# tachometer.net
KiCad netlist of a schematic drawn in Altium Designer
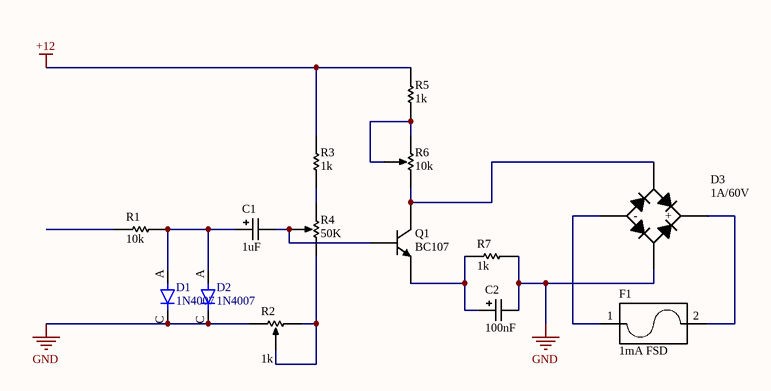
[diagram p0: tachometer.SchDoc]

(export (version "E")
  (design (tool "Eeschema 10.0.6"))
  (components
    (comp (ref "C1")
      (value "1uF")
      (footprint "CAPAE660X660R_PAN")
      (description "CAP ALUM 100UF 35V 20% SMD")
      (libsource (lib "CAP_ELE_AU_TQ_6.6X6.6_35V_PAN") (part "100uF_EEE-TQV101XAP_PAN"))
    )
    (comp (ref "C2")
      (value "100nF")
      (footprint "CAPAE660X660R_PAN")
      (description "CAP ALUM 100UF 35V 20% SMD")
      (libsource (lib "CAP_ELE_AU_TQ_6.6X6.6_35V_PAN") (part "100uF_EEE-TQV101XAP_PAN"))
    )
    (comp (ref "D1")
      (value "1N4007")
      (footprint "DIOAD1060W80L520D270")
      (description "Diode Standard 1000V 1A Through Hole DO-204AL _DO-41_")
      (fields (field (name "MF") "ON Semiconductor"))
      (libsource (lib "1N4007") (part "1N4007"))
    )
    (comp (ref "D2")
      (value "1N4007")
      (footprint "DIOAD1060W80L520D270")
      (description "Diode Standard 1000V 1A Through Hole DO-204AL _DO-41_")
      (fields (field (name "MF") "ON Semiconductor"))
      (libsource (lib "1N4007") (part "1N4007"))
    )
    (comp (ref "D3")
      (value "1A/60V")
      (footprint "SOIC127P670X270-8N_MCC")
      (description "DIODE SCHOTTKY 1A 60V MBS-1")
      (libsource (lib "DIO_BRIDGE_RECTIFIER_MB_SMD_MCC") (part "MB16S-TP_MCC"))
    )
    (comp (ref "F1")
      (value "1mA FSD")
      (footprint "NANO-452_LIT")
      (description "FUSE BOARD MNT 2A 125VAC/VDC SMD")
      (libsource (lib "FUSE_SLOW_NANO-452_LIT") (part "2A_0452002.MRL_LIT"))
    )
    (comp (ref "Q1")
      (value "BC107")
      (footprint "SOT95P230X110-3N_PHY")
      (libsource (lib "TRA_GP_NPN_SOT23_PHY") (part "BC817_SOT23"))
    )
    (comp (ref "R1")
      (value "10k")
      (footprint "RESC1508X05R_VIS")
      (description "POWER METAL STRIP RESISTOR 0.1W 1%")
      (libsource (lib "RES_MTF_AU_WSL_0603_1%_0.1W_VIS") (part "WSL0603R0150FEA_VIS"))
    )
    (comp (ref "R2")
      (value "1k")
      (footprint "TRIM_ST4ETB503_COP")
      (description "TRIMMER 5K OHM 0.25W SMD")
      (libsource (lib "POT_ST4_5mm_20%_0.25W_COP") (part "5K_ST4ETB502_COP"))
    )
    (comp (ref "R3")
      (value "1k")
      (footprint "RESC1508X05R_VIS")
      (description "POWER METAL STRIP RESISTOR 0.1W 1%")
      (libsource (lib "RES_MTF_AU_WSL_0603_1%_0.1W_VIS") (part "WSL0603R0150FEA_VIS"))
    )
    (comp (ref "R4")
      (value "50K")
      (footprint "TRIM_ST4ETB503_COP")
      (description "TRIMMER 5K OHM 0.25W SMD")
      (libsource (lib "POT_ST4_5mm_20%_0.25W_COP") (part "5K_ST4ETB502_COP"))
    )
    (comp (ref "R5")
      (value "1k")
      (footprint "RESC1508X05R_VIS")
      (description "POWER METAL STRIP RESISTOR 0.1W 1%")
      (libsource (lib "RES_MTF_AU_WSL_0603_1%_0.1W_VIS") (part "WSL0603R0150FEA_VIS"))
    )
    (comp (ref "R6")
      (value "10k")
      (footprint "TRIM_ST4ETB503_COP")
      (description "TRIMMER 5K OHM 0.25W SMD")
      (libsource (lib "POT_ST4_5mm_20%_0.25W_COP") (part "5K_ST4ETB502_COP"))
    )
    (comp (ref "R7")
      (value "1k")
      (footprint "RESC1508X05R_VIS")
      (description "POWER METAL STRIP RESISTOR 0.1W 1%")
      (libsource (lib "RES_MTF_AU_WSL_0603_1%_0.1W_VIS") (part "WSL0603R0150FEA_VIS"))
    )
  )
  (nets
    (net (code "1") (name "+12") (class "Default")
      (node (ref "R3") (pin "2") (pinfunction "2_2") (pintype "passive"))
      (node (ref "R5") (pin "2") (pinfunction "2_2") (pintype "passive"))
    )
    (net (code "2") (name "GND") (class "Default")
      (node (ref "C2") (pin "2") (pinfunction "2_2") (pintype "passive"))
      (node (ref "D1") (pin "C") (pinfunction "C_C") (pintype "passive"))
      (node (ref "D2") (pin "C") (pinfunction "C_C") (pintype "passive"))
      (node (ref "D3") (pin "2") (pinfunction "C_2") (pintype "passive"))
      (node (ref "R2") (pin "1") (pinfunction "1_1") (pintype "passive"))
      (node (ref "R7") (pin "2") (pinfunction "2_2") (pintype "passive"))
    )
    (net (code "3") (name "Net-(C1-Pad1)") (class "Default")
      (node (ref "C1") (pin "1") (pinfunction "1_1") (pintype "passive"))
      (node (ref "D1") (pin "A") (pinfunction "A_A") (pintype "passive"))
      (node (ref "D2") (pin "A") (pinfunction "A_A") (pintype "passive"))
      (node (ref "R1") (pin "2") (pinfunction "2_2") (pintype "passive"))
    )
    (net (code "4") (name "Net-(D3-+)") (class "Default")
      (node (ref "D3") (pin "1") (pinfunction "+_1") (pintype "passive"))
      (node (ref "F1") (pin "2") (pinfunction "2_2") (pintype "passive"))
    )
    (net (code "5") (name "Net-(D3--)") (class "Default")
      (node (ref "D3") (pin "3") (pinfunction "-_3") (pintype "passive"))
      (node (ref "F1") (pin "1") (pinfunction "1_1") (pintype "passive"))
    )
    (net (code "6") (name "Net-(Q1-B)") (class "Default")
      (node (ref "C1") (pin "2") (pinfunction "2_2") (pintype "passive"))
      (node (ref "Q1") (pin "1") (pinfunction "B_1") (pintype "passive"))
      (node (ref "R4") (pin "3") (pinfunction "3_3") (pintype "passive"))
    )
    (net (code "7") (name "Net-(Q1-C)") (class "Default")
      (node (ref "D3") (pin "4") (pinfunction "C_4") (pintype "passive"))
      (node (ref "Q1") (pin "3") (pinfunction "C_3") (pintype "passive"))
      (node (ref "R6") (pin "2") (pinfunction "2_2") (pintype "passive"))
    )
    (net (code "8") (name "Net-(Q1-E)") (class "Default")
      (node (ref "C2") (pin "1") (pinfunction "1_1") (pintype "passive"))
      (node (ref "Q1") (pin "2") (pinfunction "E_2") (pintype "passive"))
      (node (ref "R7") (pin "1") (pinfunction "1_1") (pintype "passive"))
    )
    (net (code "9") (name "Net-(R2-Pad2)") (class "Default")
      (node (ref "R2") (pin "2") (pinfunction "2_2") (pintype "passive"))
      (node (ref "R2") (pin "3") (pinfunction "3_3") (pintype "passive"))
      (node (ref "R4") (pin "2") (pinfunction "2_2") (pintype "passive"))
    )
    (net (code "10") (name "Net-(R3-Pad1)") (class "Default")
      (node (ref "R3") (pin "1") (pinfunction "1_1") (pintype "passive"))
      (node (ref "R4") (pin "1") (pinfunction "1_1") (pintype "passive"))
    )
    (net (code "11") (name "Net-(R5-Pad1)") (class "Default")
      (node (ref "R5") (pin "1") (pinfunction "1_1") (pintype "passive"))
      (node (ref "R6") (pin "1") (pinfunction "1_1") (pintype "passive"))
      (node (ref "R6") (pin "3") (pinfunction "3_3") (pintype "passive"))
    )
    (net (code "12") (name "unconnected-(R1-Pad1)") (class "Default")
      (node (ref "R1") (pin "1") (pinfunction "1_1") (pintype "passive"))
    )
  )
)
